# 01-PCIe.net
KiCad netlist of a schematic drawn in Altium Designer
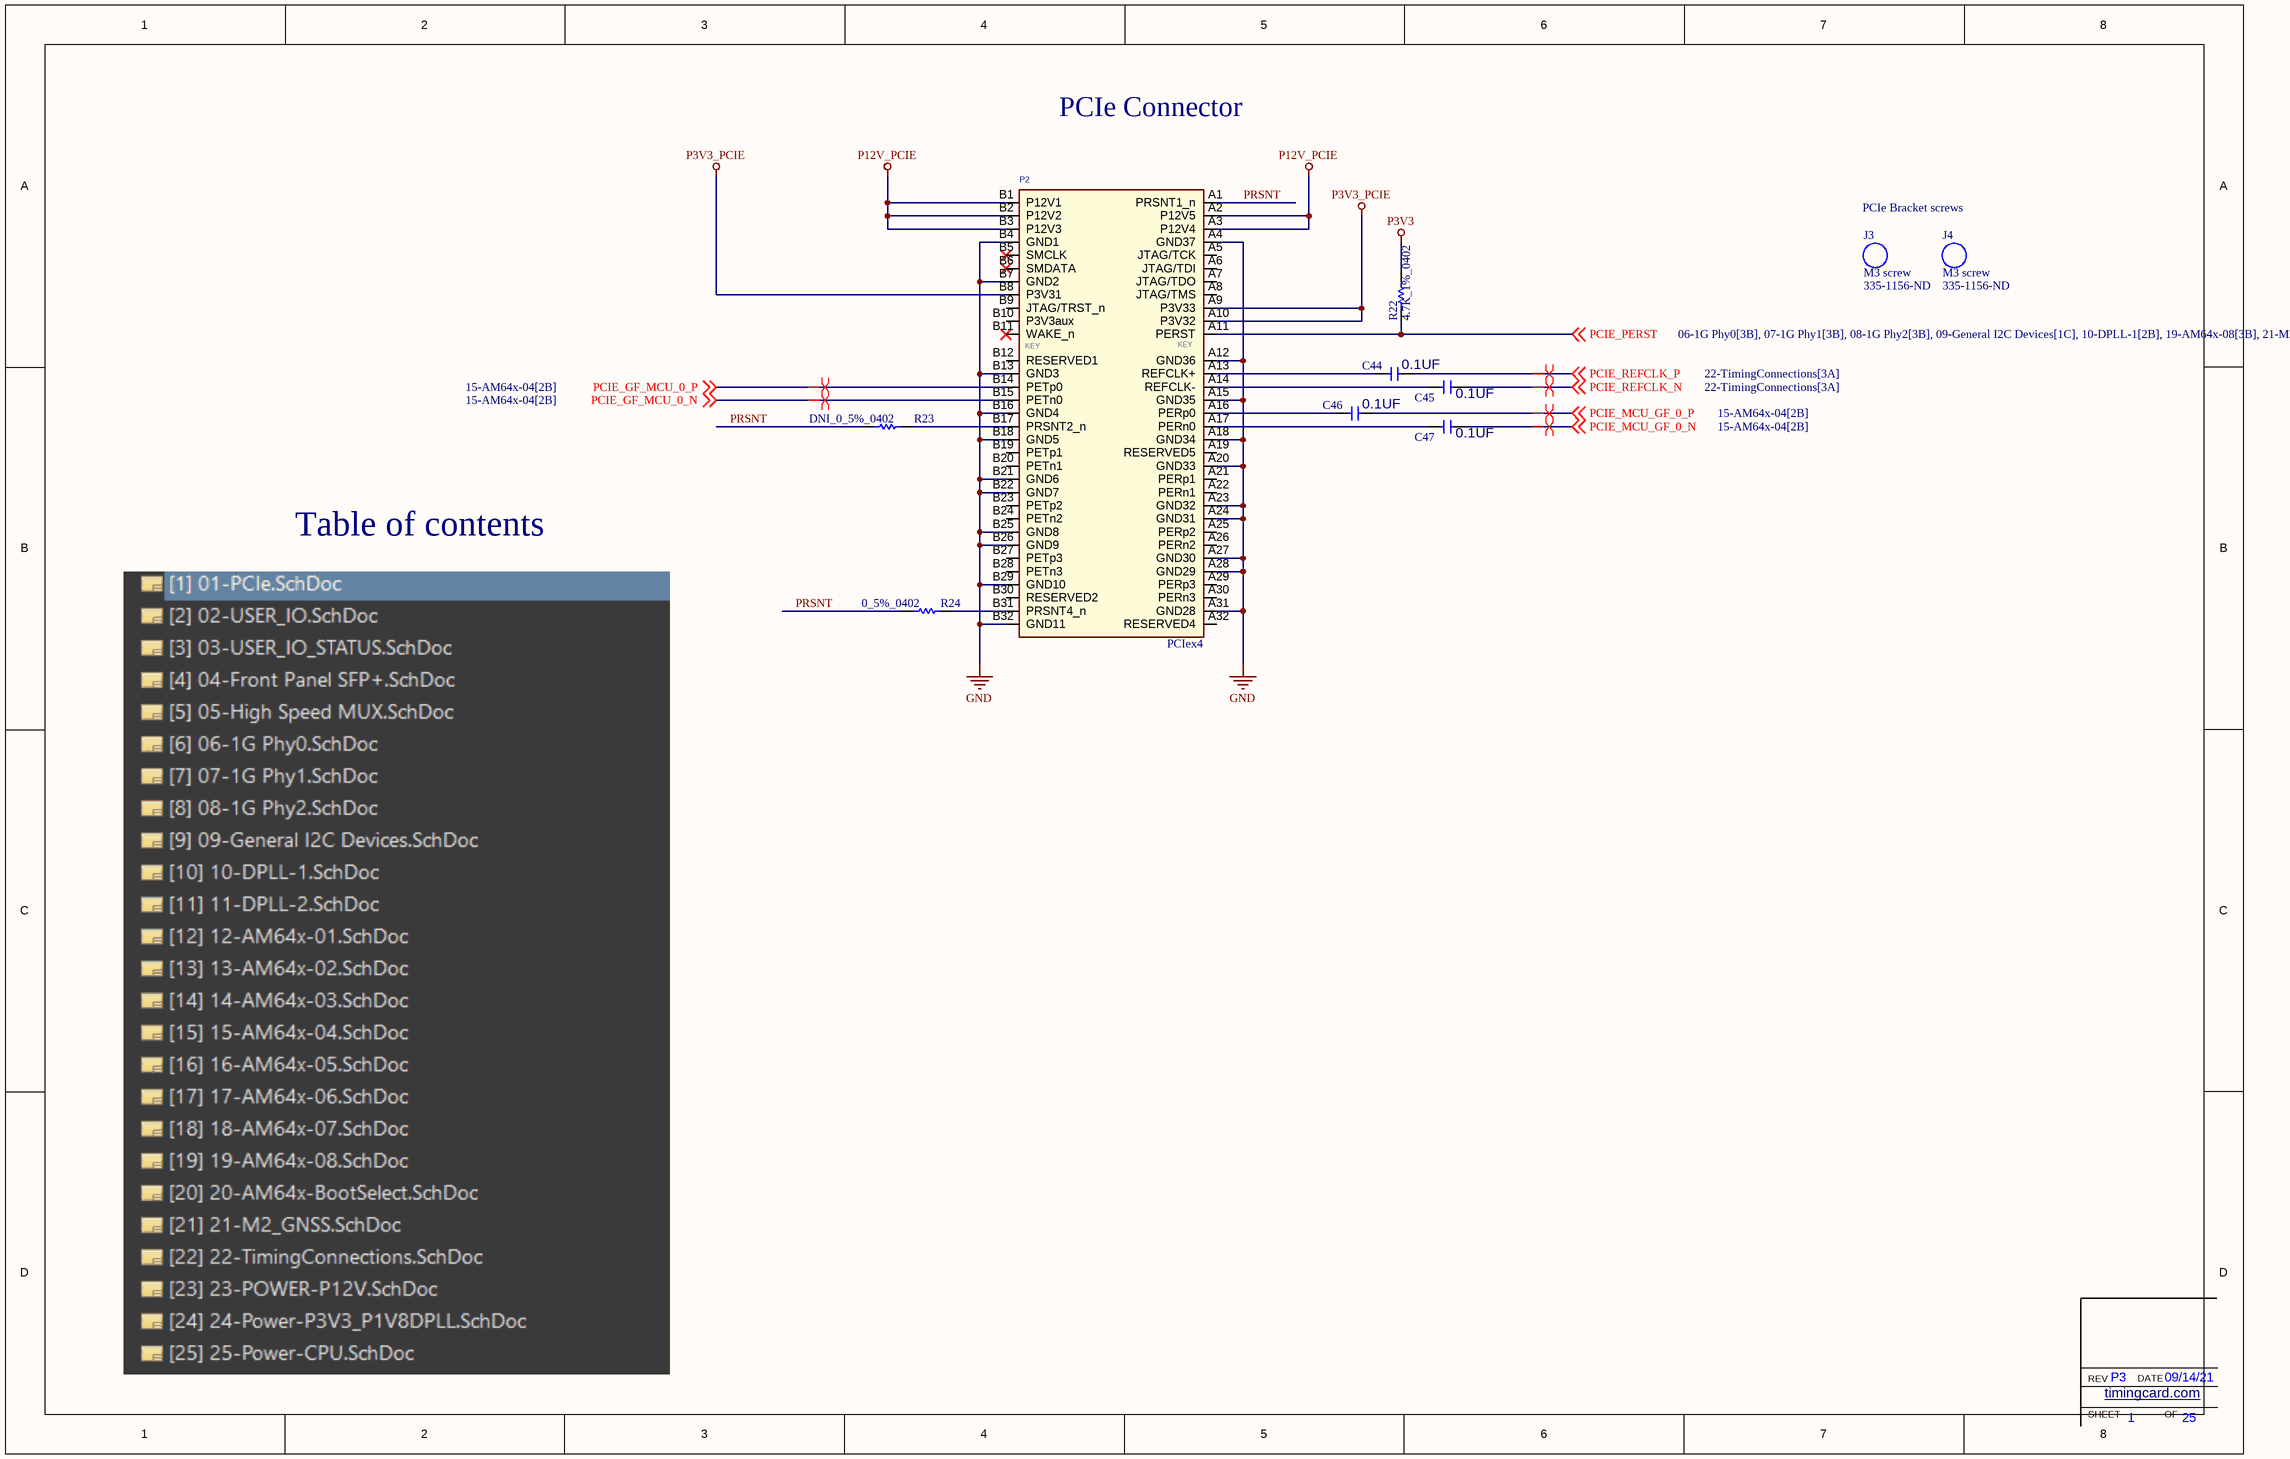
[diagram p0: 01-PCIe.SchDoc]

(export (version "E")
  (design (tool "Eeschema 10.0.6"))
  (components
    (comp (ref "C44")
      (value "0.1UF")
      (footprint "CAPC1005X06N")
      (description "CAP, CER, 0.1UF, 50V, 10%, X7R, AEC-Q200, 0402")
      (fields
        (field (name "MFG PART NUM") "CGA2B3X7R1H104K050BB")
        (field (name "VALENTIUM PART NUM") "<VALENTIUM>")
      )
      (libsource (lib "Capacitors") (part "CAP_0402_0.1UF_50V"))
    )
    (comp (ref "C45")
      (value "0.1UF")
      (footprint "CAPC1005X06N")
      (description "CAP, CER, 0.1UF, 50V, 10%, X7R, AEC-Q200, 0402")
      (fields
        (field (name "MFG PART NUM") "CGA2B3X7R1H104K050BB")
        (field (name "VALENTIUM PART NUM") "<VALENTIUM>")
      )
      (libsource (lib "Capacitors") (part "CAP_0402_0.1UF_50V"))
    )
    (comp (ref "C46")
      (value "0.1UF")
      (footprint "CAPC1005X06N")
      (description "CAP, CER, 0.1UF, 50V, 10%, X7R, AEC-Q200, 0402")
      (fields
        (field (name "MFG PART NUM") "CGA2B3X7R1H104K050BB")
        (field (name "VALENTIUM PART NUM") "<VALENTIUM>")
      )
      (libsource (lib "Capacitors") (part "CAP_0402_0.1UF_50V"))
    )
    (comp (ref "C47")
      (value "0.1UF")
      (footprint "CAPC1005X06N")
      (description "CAP, CER, 0.1UF, 50V, 10%, X7R, AEC-Q200, 0402")
      (fields
        (field (name "MFG PART NUM") "CGA2B3X7R1H104K050BB")
        (field (name "VALENTIUM PART NUM") "<VALENTIUM>")
      )
      (libsource (lib "Capacitors") (part "CAP_0402_0.1UF_50V"))
    )
    (comp (ref "J3")
      (value "M3 screw")
      (fields (field (name "SUPPLIER PART NUMBER 1") "335-1156-ND"))
      (libsource (lib "FPGA_CONN") (part "M3 screw"))
    )
    (comp (ref "J4")
      (value "M3 screw")
      (fields (field (name "SUPPLIER PART NUMBER 1") "335-1156-ND"))
      (libsource (lib "FPGA_CONN") (part "M3 screw"))
    )
    (comp (ref "P2")
      (value "PCIex4")
      (footprint "PCIE_4LANE_EDGE")
      (description "PCIE x4 Edge Connector,OrCAD Symbol,NC")
      (fields (field (name "PART NUMBER") "451") (field (name "MANUFACTURER") "NA"))
      (libsource (lib "Connectors") (part "PCIex4"))
    )
    (comp (ref "R22")
      (value "4.7K_1%_0402")
      (footprint "RESC1005X40X25NL10T10")
      (fields (field (name "MANUFACTURER") "Bourns") (field (name "PART NUMBER") "CR0402-FX-4701GLF"))
      (libsource (lib "Altium Content Vault") (part "RES"))
    )
    (comp (ref "R23")
      (value "DNI_0_5%_0402")
      (footprint "RESC1005X40X25LL10T10")
      (fields (field (name "MANUFACTURER") "KOA Speer") (field (name "PART NUMBER") "RK73Z1ETTP"))
      (libsource (lib "Altium Content Vault") (part "RES"))
    )
    (comp (ref "R24")
      (value "0_5%_0402")
      (footprint "RESC1005X40X25LL10T10")
      (fields (field (name "MANUFACTURER") "KOA Speer") (field (name "PART NUMBER") "RK73Z1ETTP"))
      (libsource (lib "Altium Content Vault") (part "RES"))
    )
  )
  (nets
    (net (code "1") (name "/PRSNT") (class "Default")
      (node (ref "P2") (pin "A1") (pinfunction "PRSNT1_n_A1") (pintype "passive"))
      (node (ref "R23") (pin "1") (pinfunction "1_1") (pintype "passive"))
      (node (ref "R24") (pin "1") (pinfunction "1_1") (pintype "passive"))
    )
    (net (code "2") (name "GND") (class "Default")
      (node (ref "P2") (pin "A12") (pinfunction "GND36_A12") (pintype "power_in"))
      (node (ref "P2") (pin "A15") (pinfunction "GND35_A15") (pintype "power_in"))
      (node (ref "P2") (pin "A18") (pinfunction "GND34_A18") (pintype "power_in"))
      (node (ref "P2") (pin "A20") (pinfunction "GND33_A20") (pintype "power_in"))
      (node (ref "P2") (pin "A23") (pinfunction "GND32_A23") (pintype "power_in"))
      (node (ref "P2") (pin "A24") (pinfunction "GND31_A24") (pintype "power_in"))
      (node (ref "P2") (pin "A27") (pinfunction "GND30_A27") (pintype "power_in"))
      (node (ref "P2") (pin "A28") (pinfunction "GND29_A28") (pintype "power_in"))
      (node (ref "P2") (pin "A31") (pinfunction "GND28_A31") (pintype "power_in"))
      (node (ref "P2") (pin "A4") (pinfunction "GND37_A4") (pintype "power_in"))
      (node (ref "P2") (pin "B13") (pinfunction "GND3_B13") (pintype "power_in"))
      (node (ref "P2") (pin "B16") (pinfunction "GND4_B16") (pintype "power_in"))
      (node (ref "P2") (pin "B18") (pinfunction "GND5_B18") (pintype "power_in"))
      (node (ref "P2") (pin "B21") (pinfunction "GND6_B21") (pintype "power_in"))
      (node (ref "P2") (pin "B22") (pinfunction "GND7_B22") (pintype "power_in"))
      (node (ref "P2") (pin "B25") (pinfunction "GND8_B25") (pintype "power_in"))
      (node (ref "P2") (pin "B26") (pinfunction "GND9_B26") (pintype "power_in"))
      (node (ref "P2") (pin "B29") (pinfunction "GND10_B29") (pintype "power_in"))
      (node (ref "P2") (pin "B32") (pinfunction "GND11_B32") (pintype "power_in"))
      (node (ref "P2") (pin "B4") (pinfunction "GND1_B4") (pintype "power_in"))
      (node (ref "P2") (pin "B7") (pinfunction "GND2_B7") (pintype "power_in"))
    )
    (net (code "3") (name "Net-(P2-PERn0)") (class "Default")
      (node (ref "C47") (pin "1") (pinfunction "1_1") (pintype "passive"))
      (node (ref "P2") (pin "A17") (pinfunction "PERn0_A17") (pintype "passive"))
    )
    (net (code "4") (name "Net-(P2-PERp0)") (class "Default")
      (node (ref "C46") (pin "1") (pinfunction "1_1") (pintype "passive"))
      (node (ref "P2") (pin "A16") (pinfunction "PERp0_A16") (pintype "passive"))
    )
    (net (code "5") (name "Net-(P2-PRSNT2_n)") (class "Default")
      (node (ref "P2") (pin "B17") (pinfunction "PRSNT2_n_B17") (pintype "passive"))
      (node (ref "R23") (pin "2") (pinfunction "2_2") (pintype "passive"))
    )
    (net (code "6") (name "Net-(P2-PRSNT4_n)") (class "Default")
      (node (ref "P2") (pin "B31") (pinfunction "PRSNT4_n_B31") (pintype "passive"))
      (node (ref "R24") (pin "2") (pinfunction "2_2") (pintype "passive"))
    )
    (net (code "7") (name "Net-(P2-REFCLK+)") (class "Default")
      (node (ref "C44") (pin "1") (pinfunction "1_1") (pintype "passive"))
      (node (ref "P2") (pin "A13") (pinfunction "REFCLK+_A13") (pintype "passive"))
    )
    (net (code "8") (name "Net-(P2-REFCLK-)") (class "Default")
      (node (ref "C45") (pin "1") (pinfunction "1_1") (pintype "passive"))
      (node (ref "P2") (pin "A14") (pinfunction "REFCLK-_A14") (pintype "passive"))
    )
    (net (code "9") (name "P3V3") (class "Default")
      (node (ref "R22") (pin "2") (pinfunction "2_2") (pintype "passive"))
    )
    (net (code "10") (name "P3V3_PCIE") (class "Default")
      (node (ref "P2") (pin "A10") (pinfunction "P3V32_A10") (pintype "passive"))
      (node (ref "P2") (pin "A9") (pinfunction "P3V33_A9") (pintype "passive"))
      (node (ref "P2") (pin "B8") (pinfunction "P3V31_B8") (pintype "power_in"))
    )
    (net (code "11") (name "P12V_PCIE") (class "Default")
      (node (ref "P2") (pin "A2") (pinfunction "P12V5_A2") (pintype "passive"))
      (node (ref "P2") (pin "A3") (pinfunction "P12V4_A3") (pintype "passive"))
      (node (ref "P2") (pin "B1") (pinfunction "P12V1_B1") (pintype "power_in"))
      (node (ref "P2") (pin "B2") (pinfunction "P12V2_B2") (pintype "power_in"))
      (node (ref "P2") (pin "B3") (pinfunction "P12V3_B3") (pintype "power_in"))
    )
    (net (code "12") (name "PCIE_GF_MCU_0_N") (class "Default")
      (node (ref "P2") (pin "B15") (pinfunction "PETn0_B15") (pintype "passive"))
    )
    (net (code "13") (name "PCIE_GF_MCU_0_P") (class "Default")
      (node (ref "P2") (pin "B14") (pinfunction "PETp0_B14") (pintype "passive"))
    )
    (net (code "14") (name "PCIE_MCU_GF_0_N") (class "Default")
      (node (ref "C47") (pin "2") (pinfunction "2_2") (pintype "passive"))
    )
    (net (code "15") (name "PCIE_MCU_GF_0_P") (class "Default")
      (node (ref "C46") (pin "2") (pinfunction "2_2") (pintype "passive"))
    )
    (net (code "16") (name "PCIE_PERST") (class "Default")
      (node (ref "P2") (pin "A11") (pinfunction "PERST_A11") (pintype "passive"))
      (node (ref "R22") (pin "1") (pinfunction "1_1") (pintype "passive"))
    )
    (net (code "17") (name "PCIE_REFCLK_N") (class "Default")
      (node (ref "C45") (pin "2") (pinfunction "2_2") (pintype "passive"))
    )
    (net (code "18") (name "PCIE_REFCLK_P") (class "Default")
      (node (ref "C44") (pin "2") (pinfunction "2_2") (pintype "passive"))
    )
    (net (code "19") (name "unconnected-(P2-JTAG{slash}TCK-PadA5)") (class "Default")
      (node (ref "P2") (pin "A5") (pinfunction "JTAG/TCK_A5") (pintype "passive"))
    )
    (net (code "20") (name "unconnected-(P2-JTAG{slash}TDI-PadA6)") (class "Default")
      (node (ref "P2") (pin "A6") (pinfunction "JTAG/TDI_A6") (pintype "passive"))
    )
    (net (code "21") (name "unconnected-(P2-JTAG{slash}TDO-PadA7)") (class "Default")
      (node (ref "P2") (pin "A7") (pinfunction "JTAG/TDO_A7") (pintype "passive"))
    )
    (net (code "22") (name "unconnected-(P2-JTAG{slash}TMS-PadA8)") (class "Default")
      (node (ref "P2") (pin "A8") (pinfunction "JTAG/TMS_A8") (pintype "passive"))
    )
    (net (code "23") (name "unconnected-(P2-JTAG{slash}TRST_n-PadB9)") (class "Default")
      (node (ref "P2") (pin "B9") (pinfunction "JTAG/TRST_n_B9") (pintype "passive"))
    )
    (net (code "24") (name "unconnected-(P2-P3V3aux-PadB10)") (class "Default")
      (node (ref "P2") (pin "B10") (pinfunction "P3V3aux_B10") (pintype "passive"))
    )
    (net (code "25") (name "unconnected-(P2-PERn1-PadA22)") (class "Default")
      (node (ref "P2") (pin "A22") (pinfunction "PERn1_A22") (pintype "passive"))
    )
    (net (code "26") (name "unconnected-(P2-PERn2-PadA26)") (class "Default")
      (node (ref "P2") (pin "A26") (pinfunction "PERn2_A26") (pintype "passive"))
    )
    (net (code "27") (name "unconnected-(P2-PERn3-PadA30)") (class "Default")
      (node (ref "P2") (pin "A30") (pinfunction "PERn3_A30") (pintype "passive"))
    )
    (net (code "28") (name "unconnected-(P2-PERp1-PadA21)") (class "Default")
      (node (ref "P2") (pin "A21") (pinfunction "PERp1_A21") (pintype "passive"))
    )
    (net (code "29") (name "unconnected-(P2-PERp2-PadA25)") (class "Default")
      (node (ref "P2") (pin "A25") (pinfunction "PERp2_A25") (pintype "passive"))
    )
    (net (code "30") (name "unconnected-(P2-PERp3-PadA29)") (class "Default")
      (node (ref "P2") (pin "A29") (pinfunction "PERp3_A29") (pintype "passive"))
    )
    (net (code "31") (name "unconnected-(P2-PETn1-PadB20)") (class "Default")
      (node (ref "P2") (pin "B20") (pinfunction "PETn1_B20") (pintype "passive"))
    )
    (net (code "32") (name "unconnected-(P2-PETn2-PadB24)") (class "Default")
      (node (ref "P2") (pin "B24") (pinfunction "PETn2_B24") (pintype "passive"))
    )
    (net (code "33") (name "unconnected-(P2-PETn3-PadB28)") (class "Default")
      (node (ref "P2") (pin "B28") (pinfunction "PETn3_B28") (pintype "passive"))
    )
    (net (code "34") (name "unconnected-(P2-PETp1-PadB19)") (class "Default")
      (node (ref "P2") (pin "B19") (pinfunction "PETp1_B19") (pintype "passive"))
    )
    (net (code "35") (name "unconnected-(P2-PETp2-PadB23)") (class "Default")
      (node (ref "P2") (pin "B23") (pinfunction "PETp2_B23") (pintype "passive"))
    )
    (net (code "36") (name "unconnected-(P2-PETp3-PadB27)") (class "Default")
      (node (ref "P2") (pin "B27") (pinfunction "PETp3_B27") (pintype "passive"))
    )
    (net (code "37") (name "unconnected-(P2-RESERVED1-PadB12)") (class "Default")
      (node (ref "P2") (pin "B12") (pinfunction "RESERVED1_B12") (pintype "passive"))
    )
    (net (code "38") (name "unconnected-(P2-RESERVED2-PadB30)") (class "Default")
      (node (ref "P2") (pin "B30") (pinfunction "RESERVED2_B30") (pintype "passive"))
    )
    (net (code "39") (name "unconnected-(P2-RESERVED4-PadA32)") (class "Default")
      (node (ref "P2") (pin "A32") (pinfunction "RESERVED4_A32") (pintype "passive"))
    )
    (net (code "40") (name "unconnected-(P2-RESERVED5-PadA19)") (class "Default")
      (node (ref "P2") (pin "A19") (pinfunction "RESERVED5_A19") (pintype "passive"))
    )
    (net (code "41") (name "unconnected-(P2-SMCLK-PadB5)") (class "Default")
      (node (ref "P2") (pin "B5") (pinfunction "SMCLK_B5") (pintype "passive+no_connect"))
    )
    (net (code "42") (name "unconnected-(P2-SMDATA-PadB6)") (class "Default")
      (node (ref "P2") (pin "B6") (pinfunction "SMDATA_B6") (pintype "passive+no_connect"))
    )
    (net (code "43") (name "unconnected-(P2-WAKE_n-PadB11)") (class "Default")
      (node (ref "P2") (pin "B11") (pinfunction "WAKE_n_B11") (pintype "passive+no_connect"))
    )
  )
)
